# plsoxmeter.net
KiCad netlist of a schematic drawn in Altium Designer
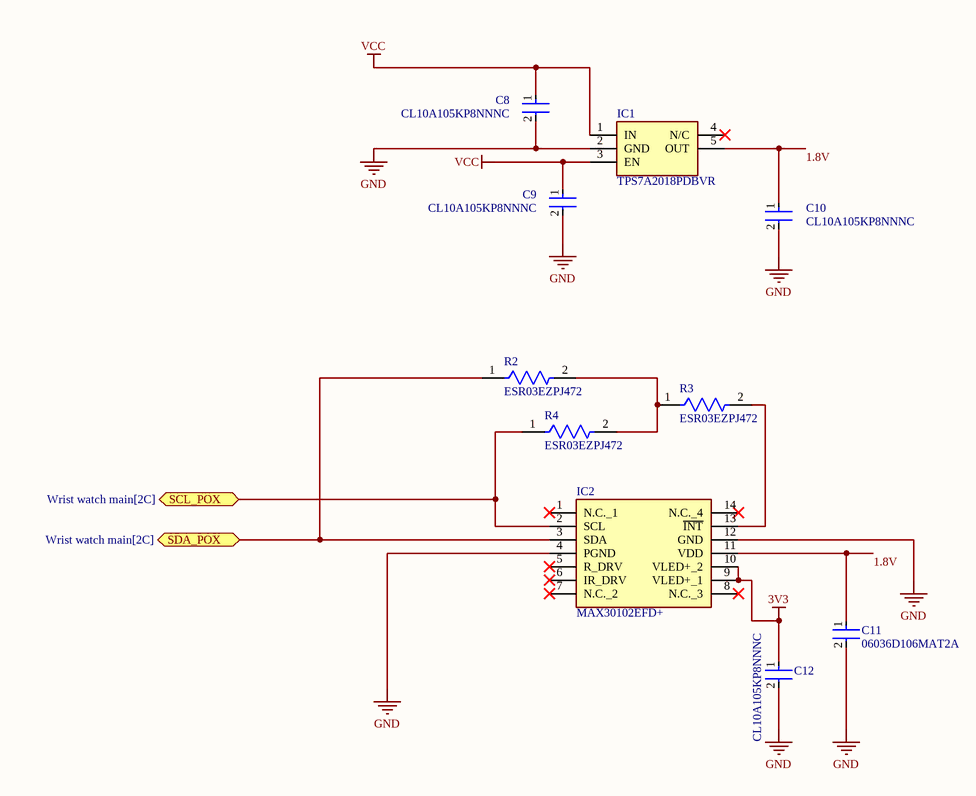
[diagram p0: plsoxmeter.SchDoc]

(export (version "E")
  (design (tool "Eeschema 10.0.6"))
  (components
    (comp (ref "C8")
      (value "CL10A105KP8NNNC")
      (footprint "FP-CL10-IPC_C")
      (description "Cap Ceramic 1uF 10V X5R ±10% Pad SMD 0603 +85°C T/R")
      (fields (field (name "VOLTAGE") "10V") (field (name "TOLERANCE") "10%"))
      (libsource (lib "Altium Content Vault") (part "b4654b650e69147ec39a6b967a45e02"))
    )
    (comp (ref "C9")
      (value "CL10A105KP8NNNC")
      (footprint "FP-CL10-IPC_C")
      (description "Cap Ceramic 1uF 10V X5R ±10% Pad SMD 0603 +85°C T/R")
      (fields (field (name "VOLTAGE") "10V") (field (name "TOLERANCE") "10%"))
      (libsource (lib "Altium Content Vault") (part "b4654b650e69147ec39a6b967a45e02"))
    )
    (comp (ref "C10")
      (value "CL10A105KP8NNNC")
      (footprint "FP-CL10-IPC_C")
      (description "Cap Ceramic 1uF 10V X5R ±10% Pad SMD 0603 +85°C T/R")
      (fields (field (name "VOLTAGE") "10V") (field (name "TOLERANCE") "10%"))
      (libsource (lib "Altium Content Vault") (part "b4654b650e69147ec39a6b967a45e02"))
    )
    (comp (ref "C11")
      (value "06036D106MAT2A")
      (footprint "FP-0603-L_1_6_0_15-W_0_81-IPC_B")
      (description "General Purpose Ceramic Capacitor, 0603, 10uF, 20%, X5R, 15%, 6.3V")
      (fields (field (name "TOLERANCE") "20%") (field (name "VOLTAGE") "6.3V"))
      (libsource (lib "Altium Content Vault") (part "02cd4be3c70576c341d710602a673aa"))
    )
    (comp (ref "C12")
      (value "CL10A105KP8NNNC")
      (footprint "FP-CL10-IPC_C")
      (description "Cap Ceramic 1uF 10V X5R ±10% Pad SMD 0603 +85°C T/R")
      (fields (field (name "VOLTAGE") "10V") (field (name "TOLERANCE") "10%"))
      (libsource (lib "Altium Content Vault") (part "b4654b650e69147ec39a6b967a45e02"))
    )
    (comp (ref "IC1")
      (value "TPS7A2018PDBVR")
      (footprint "SamacSys:SOT95P280X145-5N")
      (description "Integrated Circuit")
      (fields (field (name "MOUSER PART NUMBER") "595-TPS7A2018PDBVR"))
      (libsource (lib "*") (part "TPS7A2018PDBVR"))
    )
    (comp (ref "IC2")
      (value "MAX30102EFD+")
      (footprint "SamacSys:14-LEAD-OESIP")
      (description "Integrated Circuit")
      (fields (field (name "MOUSER PART NUMBER") "700-MAX30102EFD+"))
      (libsource (lib "*") (part "MAX30102EFD+"))
    )
    (comp (ref "R2")
      (value "ESR03EZPJ472")
      (footprint "FP-ESR03-IPC_A")
      (description "4.7kΩ ±5% 0.25W 0603 Anti-Surge Chip Resistor AEC-Q200")
      (fields (field (name "TOLERANCE") "5%"))
      (libsource (lib "Altium Content Vault") (part "1029c3af85768c4190bb7ad29bc67b5"))
    )
    (comp (ref "R3")
      (value "ESR03EZPJ472")
      (footprint "FP-ESR03-IPC_A")
      (description "4.7kΩ ±5% 0.25W 0603 Anti-Surge Chip Resistor AEC-Q200")
      (fields (field (name "TOLERANCE") "5%"))
      (libsource (lib "Altium Content Vault") (part "1029c3af85768c4190bb7ad29bc67b5"))
    )
    (comp (ref "R4")
      (value "ESR03EZPJ472")
      (footprint "FP-ESR03-IPC_A")
      (description "4.7kΩ ±5% 0.25W 0603 Anti-Surge Chip Resistor AEC-Q200")
      (fields (field (name "TOLERANCE") "5%"))
      (libsource (lib "Altium Content Vault") (part "1029c3af85768c4190bb7ad29bc67b5"))
    )
  )
  (nets
    (net (code "1") (name "/1.8V") (class "Default")
      (node (ref "C10") (pin "1") (pinfunction "1_1") (pintype "passive"))
      (node (ref "C11") (pin "1") (pinfunction "1_1") (pintype "passive"))
      (node (ref "IC1") (pin "5") (pinfunction "OUT_5") (pintype "passive"))
      (node (ref "IC2") (pin "11") (pinfunction "VDD_11") (pintype "passive"))
    )
    (net (code "2") (name "/SCL_POX") (class "Default")
      (node (ref "IC2") (pin "2") (pinfunction "SCL_2") (pintype "passive"))
      (node (ref "R4") (pin "1") (pinfunction "1_1") (pintype "passive"))
    )
    (net (code "3") (name "/SDA_POX") (class "Default")
      (node (ref "IC2") (pin "3") (pinfunction "SDA_3") (pintype "passive"))
      (node (ref "R2") (pin "1") (pinfunction "1_1") (pintype "passive"))
    )
    (net (code "4") (name "3V3") (class "Default")
      (node (ref "C12") (pin "1") (pinfunction "1_1") (pintype "passive"))
      (node (ref "IC2") (pin "10") (pinfunction "VLED+_2_10") (pintype "passive"))
      (node (ref "IC2") (pin "9") (pinfunction "VLED+_1_9") (pintype "passive"))
    )
    (net (code "5") (name "GND") (class "Default")
      (node (ref "C10") (pin "2") (pinfunction "2_2") (pintype "passive"))
      (node (ref "C11") (pin "2") (pinfunction "2_2") (pintype "passive"))
      (node (ref "C12") (pin "2") (pinfunction "2_2") (pintype "passive"))
      (node (ref "C8") (pin "2") (pinfunction "2_2") (pintype "passive"))
      (node (ref "C9") (pin "2") (pinfunction "2_2") (pintype "passive"))
      (node (ref "IC1") (pin "2") (pinfunction "GND_2") (pintype "passive"))
      (node (ref "IC2") (pin "12") (pinfunction "GND_12") (pintype "passive"))
      (node (ref "IC2") (pin "4") (pinfunction "PGND_4") (pintype "passive"))
    )
    (net (code "6") (name "Net-(IC2-~{INT})") (class "Default")
      (node (ref "IC2") (pin "13") (pinfunction "~{INT}_13") (pintype "passive"))
      (node (ref "R3") (pin "2") (pinfunction "2_2") (pintype "passive"))
    )
    (net (code "7") (name "Net-(R2-Pad2)") (class "Default")
      (node (ref "R2") (pin "2") (pinfunction "2_2") (pintype "passive"))
      (node (ref "R3") (pin "1") (pinfunction "1_1") (pintype "passive"))
      (node (ref "R4") (pin "2") (pinfunction "2_2") (pintype "passive"))
    )
    (net (code "8") (name "VCC") (class "Default")
      (node (ref "C8") (pin "1") (pinfunction "1_1") (pintype "passive"))
      (node (ref "C9") (pin "1") (pinfunction "1_1") (pintype "passive"))
      (node (ref "IC1") (pin "1") (pinfunction "IN_1") (pintype "passive"))
      (node (ref "IC1") (pin "3") (pinfunction "EN_3") (pintype "passive"))
    )
    (net (code "9") (name "unconnected-(IC1-N{slash}C-Pad4)") (class "Default")
      (node (ref "IC1") (pin "4") (pinfunction "N/C_4") (pintype "passive+no_connect"))
    )
    (net (code "10") (name "unconnected-(IC2-IR_DRV-Pad6)") (class "Default")
      (node (ref "IC2") (pin "6") (pinfunction "IR_DRV_6") (pintype "passive+no_connect"))
    )
    (net (code "11") (name "unconnected-(IC2-N.C._1-Pad1)") (class "Default")
      (node (ref "IC2") (pin "1") (pinfunction "N.C._1_1") (pintype "passive+no_connect"))
    )
    (net (code "12") (name "unconnected-(IC2-N.C._2-Pad7)") (class "Default")
      (node (ref "IC2") (pin "7") (pinfunction "N.C._2_7") (pintype "passive+no_connect"))
    )
    (net (code "13") (name "unconnected-(IC2-N.C._3-Pad8)") (class "Default")
      (node (ref "IC2") (pin "8") (pinfunction "N.C._3_8") (pintype "passive+no_connect"))
    )
    (net (code "14") (name "unconnected-(IC2-N.C._4-Pad14)") (class "Default")
      (node (ref "IC2") (pin "14") (pinfunction "N.C._4_14") (pintype "passive+no_connect"))
    )
    (net (code "15") (name "unconnected-(IC2-R_DRV-Pad5)") (class "Default")
      (node (ref "IC2") (pin "5") (pinfunction "R_DRV_5") (pintype "passive+no_connect"))
    )
  )
)
